# hdmi.net
KiCad netlist of a schematic drawn in Altium Designer
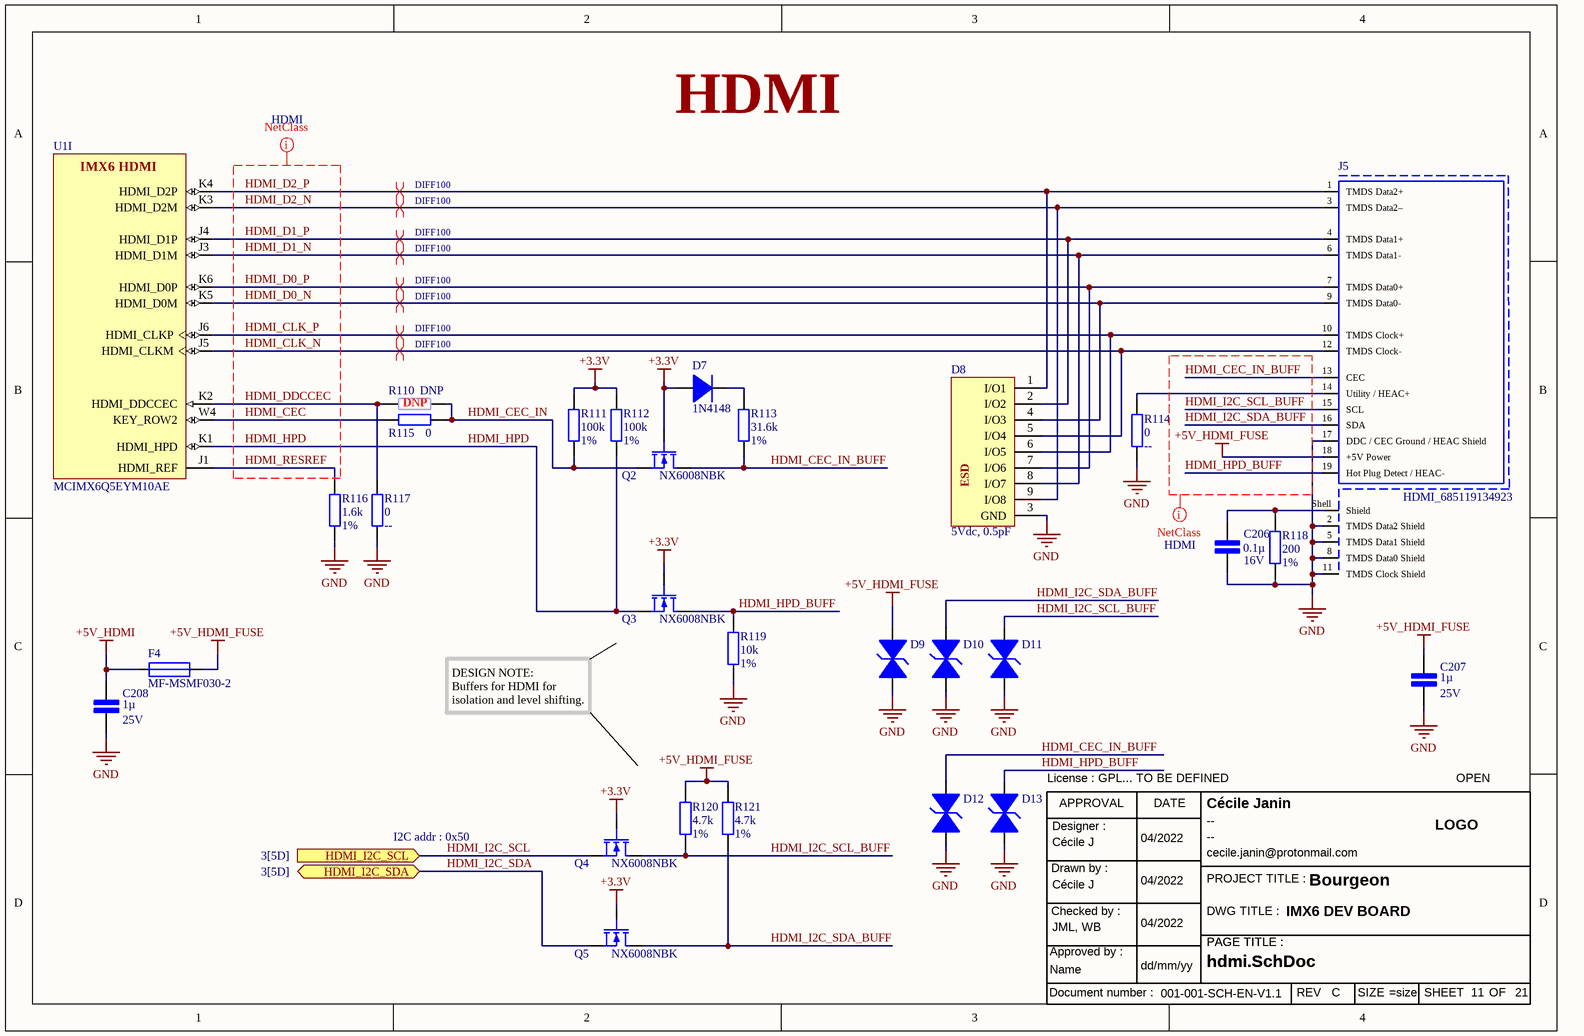
[diagram p0: hdmi.SchDoc]

(export (version "E")
  (design (tool "Eeschema 10.0.6"))
  (components
    (comp (ref "C206")
      (value "0.1µ")
      (footprint "Cap cer 0402/1005")
      (description "cap solid electrolyte 0.1µ 6.3V 10%")
      (fields (field (name "TENSION DU DIÉLECTRIQUE") "16V"))
      (libsource (lib "First Board IMX6") (part "cap 0.1µ 16V"))
    )
    (comp (ref "C207")
      (value "1µ")
      (footprint "Cap cer 0402/1005")
      (description "cap cer 1µ 25V 10% X5R 0402")
      (fields (field (name "TENSION DU DIÉLECTRIQUE") "25V"))
      (libsource (lib "First Board IMX6") (part "cap 1µ 25V"))
    )
    (comp (ref "C208")
      (value "1µ")
      (footprint "Cap cer 0402/1005")
      (description "cap cer 1µ 25V 10% X5R 0402")
      (fields (field (name "TENSION DU DIÉLECTRIQUE") "25V"))
      (libsource (lib "First Board IMX6") (part "cap 1µ 25V"))
    )
    (comp (ref "D7")
      (value "1N4148")
      (footprint "diode SOD-123")
      (libsource (lib "First Board IMX6") (part "Diode 1N4148 100V 150mA"))
    )
    (comp (ref "D8")
      (value "5Vdc, 0.5pF")
      (footprint "TVS 8 pin")
      (description "WE-TVS TVS Diode – Super Speed Series, DFN3810-9L, 8 Channel, 5Vdc, 0.5pF 824014885")
      (fields
        (field (name "MANUFACTURER PART NUMBER") "824014885")
        (field (name "MANUFACTURER") "Wurth Elektronik")
      )
      (libsource (lib "First Board IMX6") (part "TVS HDMI"))
    )
    (comp (ref "D9")
      (value "TVS 5V")
      (footprint "inductor 0402/1005")
      (description "82357120050")
      (libsource (lib "First Board IMX6") (part "TVS suppressor 82357120050"))
    )
    (comp (ref "D10")
      (value "TVS 5V")
      (footprint "inductor 0402/1005")
      (description "82357120050")
      (libsource (lib "First Board IMX6") (part "TVS suppressor 82357120050"))
    )
    (comp (ref "D11")
      (value "TVS 5V")
      (footprint "inductor 0402/1005")
      (description "82357120050")
      (libsource (lib "First Board IMX6") (part "TVS suppressor 82357120050"))
    )
    (comp (ref "D12")
      (value "TVS 5V")
      (footprint "inductor 0402/1005")
      (description "82357120050")
      (libsource (lib "First Board IMX6") (part "TVS suppressor 82357120050"))
    )
    (comp (ref "D13")
      (value "TVS 5V")
      (footprint "inductor 0402/1005")
      (description "82357120050")
      (libsource (lib "First Board IMX6") (part "TVS suppressor 82357120050"))
    )
    (comp (ref "F4")
      (value "MF-MSMF030-2")
      (footprint "Fuse 1812/4532 MF-MSMF050-2")
      (description "Hold : 0.3A, trip 0.6A 30V 1812")
      (libsource (lib "First Board IMX6") (part "Fuse PPTC 0.3A"))
    )
    (comp (ref "J5")
      (value "HDMI_685119134923")
      (footprint "HDMI_685119134923")
      (libsource (lib "First Board IMX6") (part "HDMI_685119134923"))
    )
    (comp (ref "Q2")
      (value "NX6008NBK")
      (footprint "Sot-23-3 mosfet")
      (description "SOT-23-3 270mA 60V ESD protected 2kV HBM")
      (libsource (lib "First Board IMX6") (part "Tr nmos NX6008NBK"))
    )
    (comp (ref "Q3")
      (value "NX6008NBK")
      (footprint "Sot-23-3 mosfet")
      (description "SOT-23-3 270mA 60V ESD protected 2kV HBM")
      (libsource (lib "First Board IMX6") (part "Tr nmos NX6008NBK"))
    )
    (comp (ref "Q4")
      (value "NX6008NBK")
      (footprint "Sot-23-3 mosfet")
      (description "SOT-23-3 270mA 60V ESD protected 2kV HBM")
      (libsource (lib "First Board IMX6") (part "Tr nmos NX6008NBK"))
    )
    (comp (ref "Q5")
      (value "NX6008NBK")
      (footprint "Sot-23-3 mosfet")
      (description "SOT-23-3 270mA 60V ESD protected 2kV HBM")
      (libsource (lib "First Board IMX6") (part "Tr nmos NX6008NBK"))
    )
    (comp (ref "R110")
      (value "DNP")
      (footprint "Res 0603/1603")
      (description "res DNP 0603")
      (libsource (lib "First Board IMX6") (part "res DNP 0603"))
    )
    (comp (ref "R111")
      (value "100k")
      (footprint "Res 0402/1005")
      (description "res 100k 1% 0402")
      (fields (field (name "POURCENTAGE") "1%"))
      (libsource (lib "First Board IMX6") (part "res 100k 1%"))
    )
    (comp (ref "R112")
      (value "100k")
      (footprint "Res 0402/1005")
      (description "res 100k 1% 0402")
      (fields (field (name "POURCENTAGE") "1%"))
      (libsource (lib "First Board IMX6") (part "res 100k 1%"))
    )
    (comp (ref "R113")
      (value "31.6k")
      (footprint "Res 0402/1005")
      (description "res 31.6k 1% 0402")
      (fields (field (name "POURCENTAGE") "1%"))
      (libsource (lib "First Board IMX6") (part "res 31.6k 1%"))
    )
    (comp (ref "R114")
      (value "0")
      (footprint "Res 0402/1005")
      (description "res 0402")
      (fields (field (name "POURCENTAGE") "--"))
      (libsource (lib "First Board IMX6") (part "res 0Ohm small"))
    )
    (comp (ref "R115")
      (value "0")
      (footprint "Res 0603/1603")
      (description "res 0603")
      (libsource (lib "First Board IMX6") (part "res 0Ohm"))
    )
    (comp (ref "R116")
      (value "1.6k")
      (footprint "Res 0402/1005")
      (description "res 1.6k 1% 0402")
      (fields (field (name "POURCENTAGE") "1%"))
      (libsource (lib "First Board IMX6") (part "res 1.6k 1%"))
    )
    (comp (ref "R117")
      (value "0")
      (footprint "Res 0603/1603")
      (description "res 0603")
      (fields (field (name "POURCENTAGE") "--"))
      (libsource (lib "First Board IMX6") (part "res 0Ohm"))
    )
    (comp (ref "R118")
      (value "200")
      (footprint "Res 0402/1005")
      (description "res 200 1% 0402")
      (fields (field (name "POURCENTAGE") "1%"))
      (libsource (lib "First Board IMX6") (part "res 200 1%"))
    )
    (comp (ref "R119")
      (value "10k")
      (footprint "Res 0402/1005")
      (description "res 10k 1% 0402")
      (fields (field (name "POURCENTAGE") "1%"))
      (libsource (lib "First Board IMX6") (part "res 10k 1%"))
    )
    (comp (ref "R120")
      (value "4.7k")
      (footprint "Res 0402/1005")
      (description "res 4.7k 1% 0402")
      (fields (field (name "POURCENTAGE") "1%"))
      (libsource (lib "First Board IMX6") (part "res 4.7k 1%"))
    )
    (comp (ref "R121")
      (value "4.7k")
      (footprint "Res 0402/1005")
      (description "res 4.7k 1% 0402")
      (fields (field (name "POURCENTAGE") "1%"))
      (libsource (lib "First Board IMX6") (part "res 4.7k 1%"))
    )
    (comp (ref "TB10")
      (value "Title bloc ANSI modified")
      (libsource (lib "First Board IMX6") (part "Title bloc ANSI"))
    )
    (comp (ref "U1")
      (value "MCIMX6Q5EYM10AE")
      (footprint "FRES-2197-01")
      (fields
        (field (name "PARTNUMBER") "MCIMX6Q5EYM10ACR")
        (field (name "MANUFACTURER") "Freescale Semiconductor")
      )
      (libsource (lib "First Board IMX6") (part "IMX6Q5EYM10AE"))
    )
  )
  (nets
    (net (code "1") (name "+3.3V") (class "Default")
      (node (ref "D7") (pin "A") (pintype "passive"))
      (node (ref "Q2") (pin "G") (pinfunction "G_G") (pintype "passive"))
      (node (ref "Q3") (pin "G") (pinfunction "G_G") (pintype "passive"))
      (node (ref "Q4") (pin "G") (pinfunction "G_G") (pintype "passive"))
      (node (ref "Q5") (pin "G") (pinfunction "G_G") (pintype "passive"))
      (node (ref "R111") (pin "2") (pintype "passive"))
      (node (ref "R112") (pin "2") (pintype "passive"))
    )
    (net (code "2") (name "+5V_HDMI") (class "Default")
      (node (ref "C208") (pin "1") (pinfunction "3_1") (pintype "passive"))
      (node (ref "F4") (pin "1") (pinfunction "1_1") (pintype "passive"))
    )
    (net (code "3") (name "+5V_HDMI_FUSE") (class "Default")
      (node (ref "C207") (pin "1") (pinfunction "3_1") (pintype "passive"))
      (node (ref "D9") (pin "1") (pintype "passive"))
      (node (ref "F4") (pin "2") (pinfunction "2_2") (pintype "passive"))
      (node (ref "J5") (pin "18") (pinfunction "+5V_Power_18") (pintype "passive"))
      (node (ref "R120") (pin "2") (pintype "passive"))
      (node (ref "R121") (pin "2") (pintype "passive"))
    )
    (net (code "4") (name "/HDMI_CEC") (class "Default")
      (node (ref "R115") (pin "1") (pintype "passive"))
      (node (ref "U1") (pin "W4") (pinfunction "KEY_ROW2_W4") (pintype "bidirectional"))
    )
    (net (code "5") (name "/HDMI_CEC_IN") (class "Default")
      (node (ref "Q2") (pin "S") (pinfunction "S_S") (pintype "passive"))
      (node (ref "R110") (pin "2") (pintype "passive"))
      (node (ref "R111") (pin "1") (pintype "passive"))
      (node (ref "R115") (pin "2") (pintype "passive"))
    )
    (net (code "6") (name "/HDMI_CEC_IN_BUFF") (class "Default")
      (node (ref "D12") (pin "1") (pintype "passive"))
      (node (ref "J5") (pin "13") (pinfunction "CEC_13") (pintype "passive"))
      (node (ref "Q2") (pin "D") (pinfunction "D_D") (pintype "passive"))
      (node (ref "R113") (pin "1") (pintype "passive"))
    )
    (net (code "7") (name "/HDMI_CLK_N") (class "Default")
      (node (ref "D8") (pin "5") (pinfunction "I/O4_5") (pintype "passive"))
      (node (ref "J5") (pin "12") (pinfunction "TMDS_Clock-_12") (pintype "passive"))
      (node (ref "U1") (pin "J5") (pinfunction "HDMI_CLKM_J5") (pintype "bidirectional"))
    )
    (net (code "8") (name "/HDMI_CLK_P") (class "Default")
      (node (ref "D8") (pin "6") (pinfunction "I/O5_6") (pintype "passive"))
      (node (ref "J5") (pin "10") (pinfunction "TMDS_Clock+_10") (pintype "passive"))
      (node (ref "U1") (pin "J6") (pinfunction "HDMI_CLKP_J6") (pintype "bidirectional"))
    )
    (net (code "9") (name "/HDMI_D0_N") (class "Default")
      (node (ref "D8") (pin "4") (pinfunction "I/O3_4") (pintype "passive"))
      (node (ref "J5") (pin "9") (pinfunction "TMDS_Data0-_9") (pintype "passive"))
      (node (ref "U1") (pin "K5") (pinfunction "HDMI_D0M_K5") (pintype "bidirectional"))
    )
    (net (code "10") (name "/HDMI_D0_P") (class "Default")
      (node (ref "D8") (pin "7") (pinfunction "I/O6_7") (pintype "passive"))
      (node (ref "J5") (pin "7") (pinfunction "TMDS_Data0+_7") (pintype "passive"))
      (node (ref "U1") (pin "K6") (pinfunction "HDMI_D0P_K6") (pintype "bidirectional"))
    )
    (net (code "11") (name "/HDMI_D1_N") (class "Default")
      (node (ref "D8") (pin "8") (pinfunction "I/O7_8") (pintype "passive"))
      (node (ref "J5") (pin "6") (pinfunction "TMDS_Data1-_6") (pintype "passive"))
      (node (ref "U1") (pin "J3") (pinfunction "HDMI_D1M_J3") (pintype "bidirectional"))
    )
    (net (code "12") (name "/HDMI_D1_P") (class "Default")
      (node (ref "D8") (pin "2") (pinfunction "I/O2_2") (pintype "passive"))
      (node (ref "J5") (pin "4") (pinfunction "TMDS_Data1+_4") (pintype "passive"))
      (node (ref "U1") (pin "J4") (pinfunction "HDMI_D1P_J4") (pintype "bidirectional"))
    )
    (net (code "13") (name "/HDMI_D2_N") (class "Default")
      (node (ref "D8") (pin "9") (pinfunction "I/O8_9") (pintype "passive"))
      (node (ref "J5") (pin "3") (pinfunction "TMDS_Data2–_3") (pintype "passive"))
      (node (ref "U1") (pin "K3") (pinfunction "HDMI_D2M_K3") (pintype "bidirectional"))
    )
    (net (code "14") (name "/HDMI_D2_P") (class "Default")
      (node (ref "D8") (pin "1") (pinfunction "I/O1_1") (pintype "passive"))
      (node (ref "J5") (pin "1") (pinfunction "TMDS_Data2+_1") (pintype "passive"))
      (node (ref "U1") (pin "K4") (pinfunction "HDMI_D2P_K4") (pintype "bidirectional"))
    )
    (net (code "15") (name "/HDMI_DDCCEC") (class "Default")
      (node (ref "R110") (pin "1") (pintype "passive"))
      (node (ref "R117") (pin "2") (pintype "passive"))
      (node (ref "U1") (pin "K2") (pinfunction "HDMI_DDCCEC_K2") (pintype "input"))
    )
    (net (code "16") (name "/HDMI_HPD") (class "Default")
      (node (ref "Q3") (pin "S") (pinfunction "S_S") (pintype "passive"))
      (node (ref "R112") (pin "1") (pintype "passive"))
      (node (ref "U1") (pin "K1") (pinfunction "HDMI_HPD_K1") (pintype "bidirectional"))
    )
    (net (code "17") (name "/HDMI_HPD_BUFF") (class "Default")
      (node (ref "D13") (pin "1") (pintype "passive"))
      (node (ref "J5") (pin "19") (pinfunction "Hot_Plug_Detect_/_HEAC-_19") (pintype "passive"))
      (node (ref "Q3") (pin "D") (pinfunction "D_D") (pintype "passive"))
      (node (ref "R119") (pin "2") (pintype "passive"))
    )
    (net (code "18") (name "/HDMI_I2C_SCL") (class "Default")
      (node (ref "Q4") (pin "S") (pinfunction "S_S") (pintype "passive"))
    )
    (net (code "19") (name "/HDMI_I2C_SCL_BUFF") (class "Default")
      (node (ref "D11") (pin "1") (pintype "passive"))
      (node (ref "J5") (pin "15") (pinfunction "SCL_15") (pintype "passive"))
      (node (ref "Q4") (pin "D") (pinfunction "D_D") (pintype "passive"))
      (node (ref "R120") (pin "1") (pintype "passive"))
    )
    (net (code "20") (name "/HDMI_I2C_SDA") (class "Default")
      (node (ref "Q5") (pin "S") (pinfunction "S_S") (pintype "passive"))
    )
    (net (code "21") (name "/HDMI_I2C_SDA_BUFF") (class "Default")
      (node (ref "D10") (pin "1") (pintype "passive"))
      (node (ref "J5") (pin "16") (pinfunction "SDA_16") (pintype "passive"))
      (node (ref "Q5") (pin "D") (pinfunction "D_D") (pintype "passive"))
      (node (ref "R121") (pin "1") (pintype "passive"))
    )
    (net (code "22") (name "/HDMI_RESREF") (class "Default")
      (node (ref "R116") (pin "2") (pintype "passive"))
      (node (ref "U1") (pin "J1") (pinfunction "HDMI_REF_J1") (pintype "passive"))
    )
    (net (code "23") (name "GND") (class "Default")
      (node (ref "C206") (pin "2") (pinfunction "4_2") (pintype "passive"))
      (node (ref "C207") (pin "2") (pinfunction "4_2") (pintype "passive"))
      (node (ref "C208") (pin "2") (pinfunction "4_2") (pintype "passive"))
      (node (ref "D10") (pin "2") (pintype "passive"))
      (node (ref "D11") (pin "2") (pintype "passive"))
      (node (ref "D12") (pin "2") (pintype "passive"))
      (node (ref "D13") (pin "2") (pintype "passive"))
      (node (ref "D8") (pin "3") (pinfunction "GND_3") (pintype "passive"))
      (node (ref "D9") (pin "2") (pintype "passive"))
      (node (ref "J5") (pin "11") (pinfunction "TMDS_Clock_Shield_11") (pintype "passive"))
      (node (ref "J5") (pin "17") (pinfunction "DDC_/_CEC_Ground_/_HEAC_Shield_17") (pintype "passive"))
      (node (ref "J5") (pin "2") (pinfunction "TMDS_Data2_Shield_2") (pintype "passive"))
      (node (ref "J5") (pin "5") (pinfunction "TMDS_Data1_Shield_5") (pintype "passive"))
      (node (ref "J5") (pin "8") (pinfunction "TMDS_Data0_Shield_8") (pintype "passive"))
      (node (ref "R114") (pin "1") (pintype "passive"))
      (node (ref "R116") (pin "1") (pintype "passive"))
      (node (ref "R117") (pin "1") (pintype "passive"))
      (node (ref "R118") (pin "1") (pintype "passive"))
      (node (ref "R119") (pin "1") (pintype "passive"))
    )
    (net (code "24") (name "Net-(C206-3)") (class "Default")
      (node (ref "C206") (pin "1") (pinfunction "3_1") (pintype "passive"))
      (node (ref "J5") (pin "Shell") (pinfunction "Shield_Shell") (pintype "passive"))
      (node (ref "R118") (pin "2") (pintype "passive"))
    )
    (net (code "25") (name "Net-(D7-PadK)") (class "Default")
      (node (ref "D7") (pin "K") (pintype "passive"))
      (node (ref "R113") (pin "2") (pintype "passive"))
    )
    (net (code "26") (name "Net-(J5-Utility_{slash}_HEAC+)") (class "Default")
      (node (ref "J5") (pin "14") (pinfunction "Utility_/_HEAC+_14") (pintype "passive"))
      (node (ref "R114") (pin "2") (pintype "passive"))
    )
  )
)
